# DC_Electronic_Load.net
KiCad netlist of a schematic drawn in EAGLE
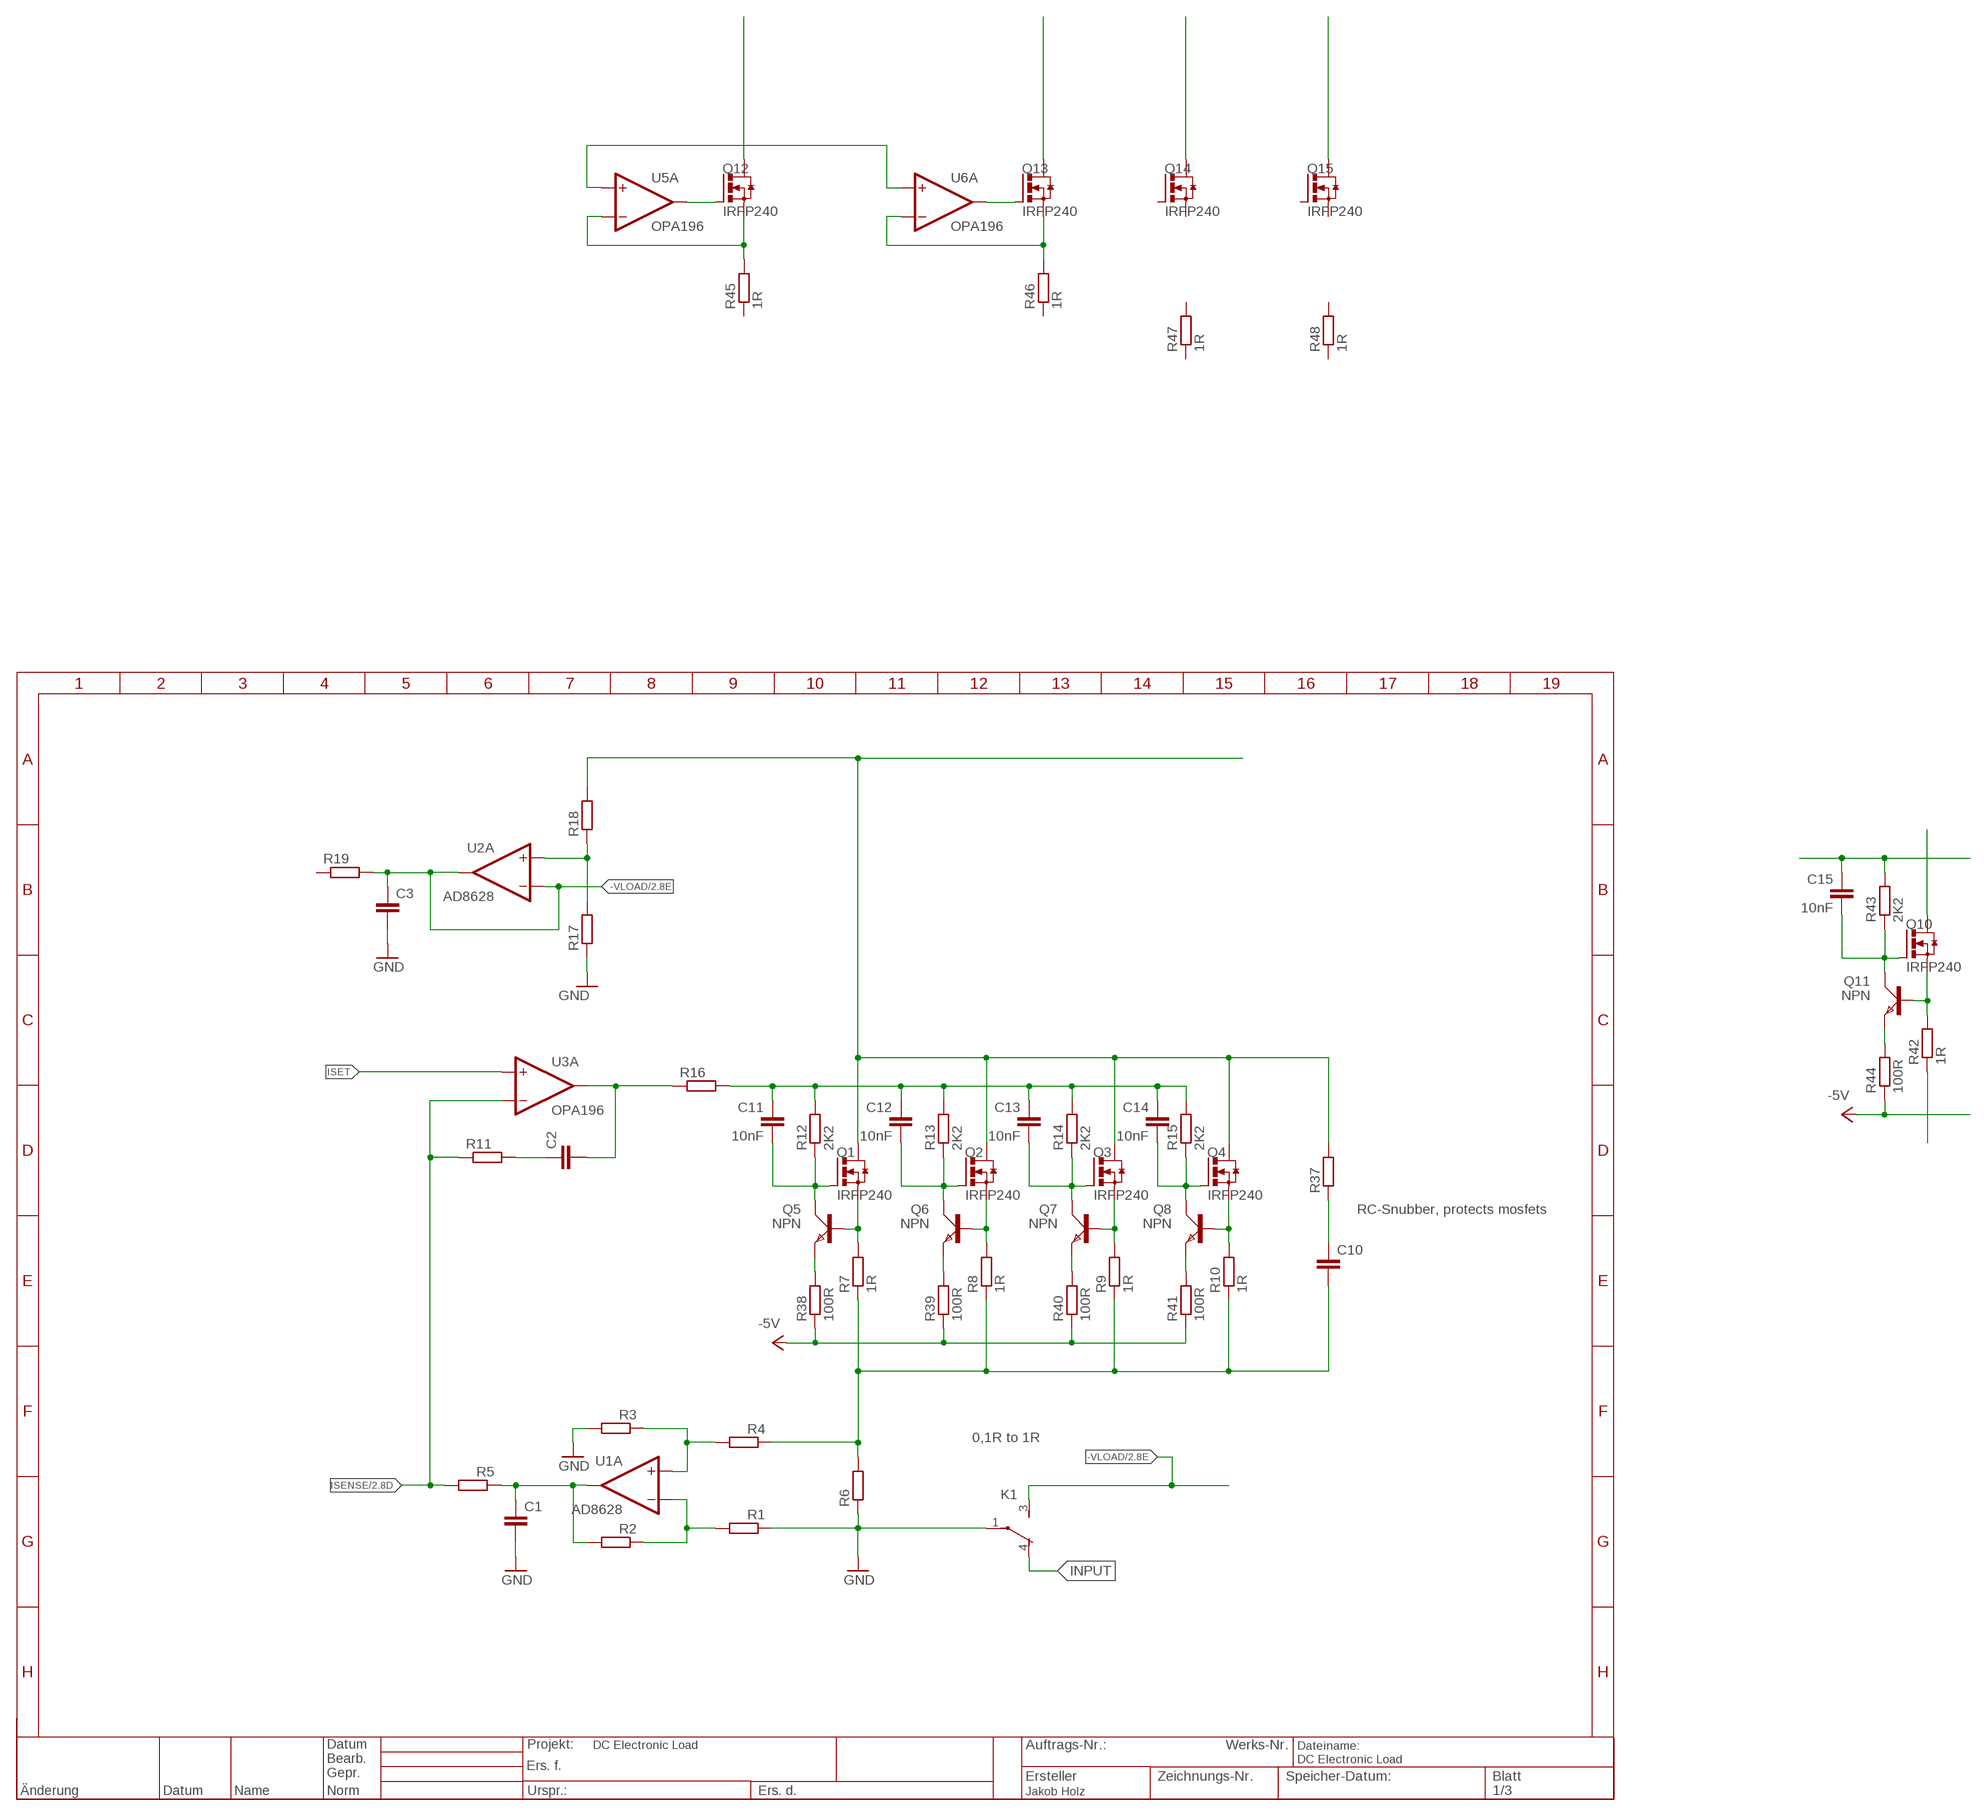
[diagram p0: schematic, sheet 1]
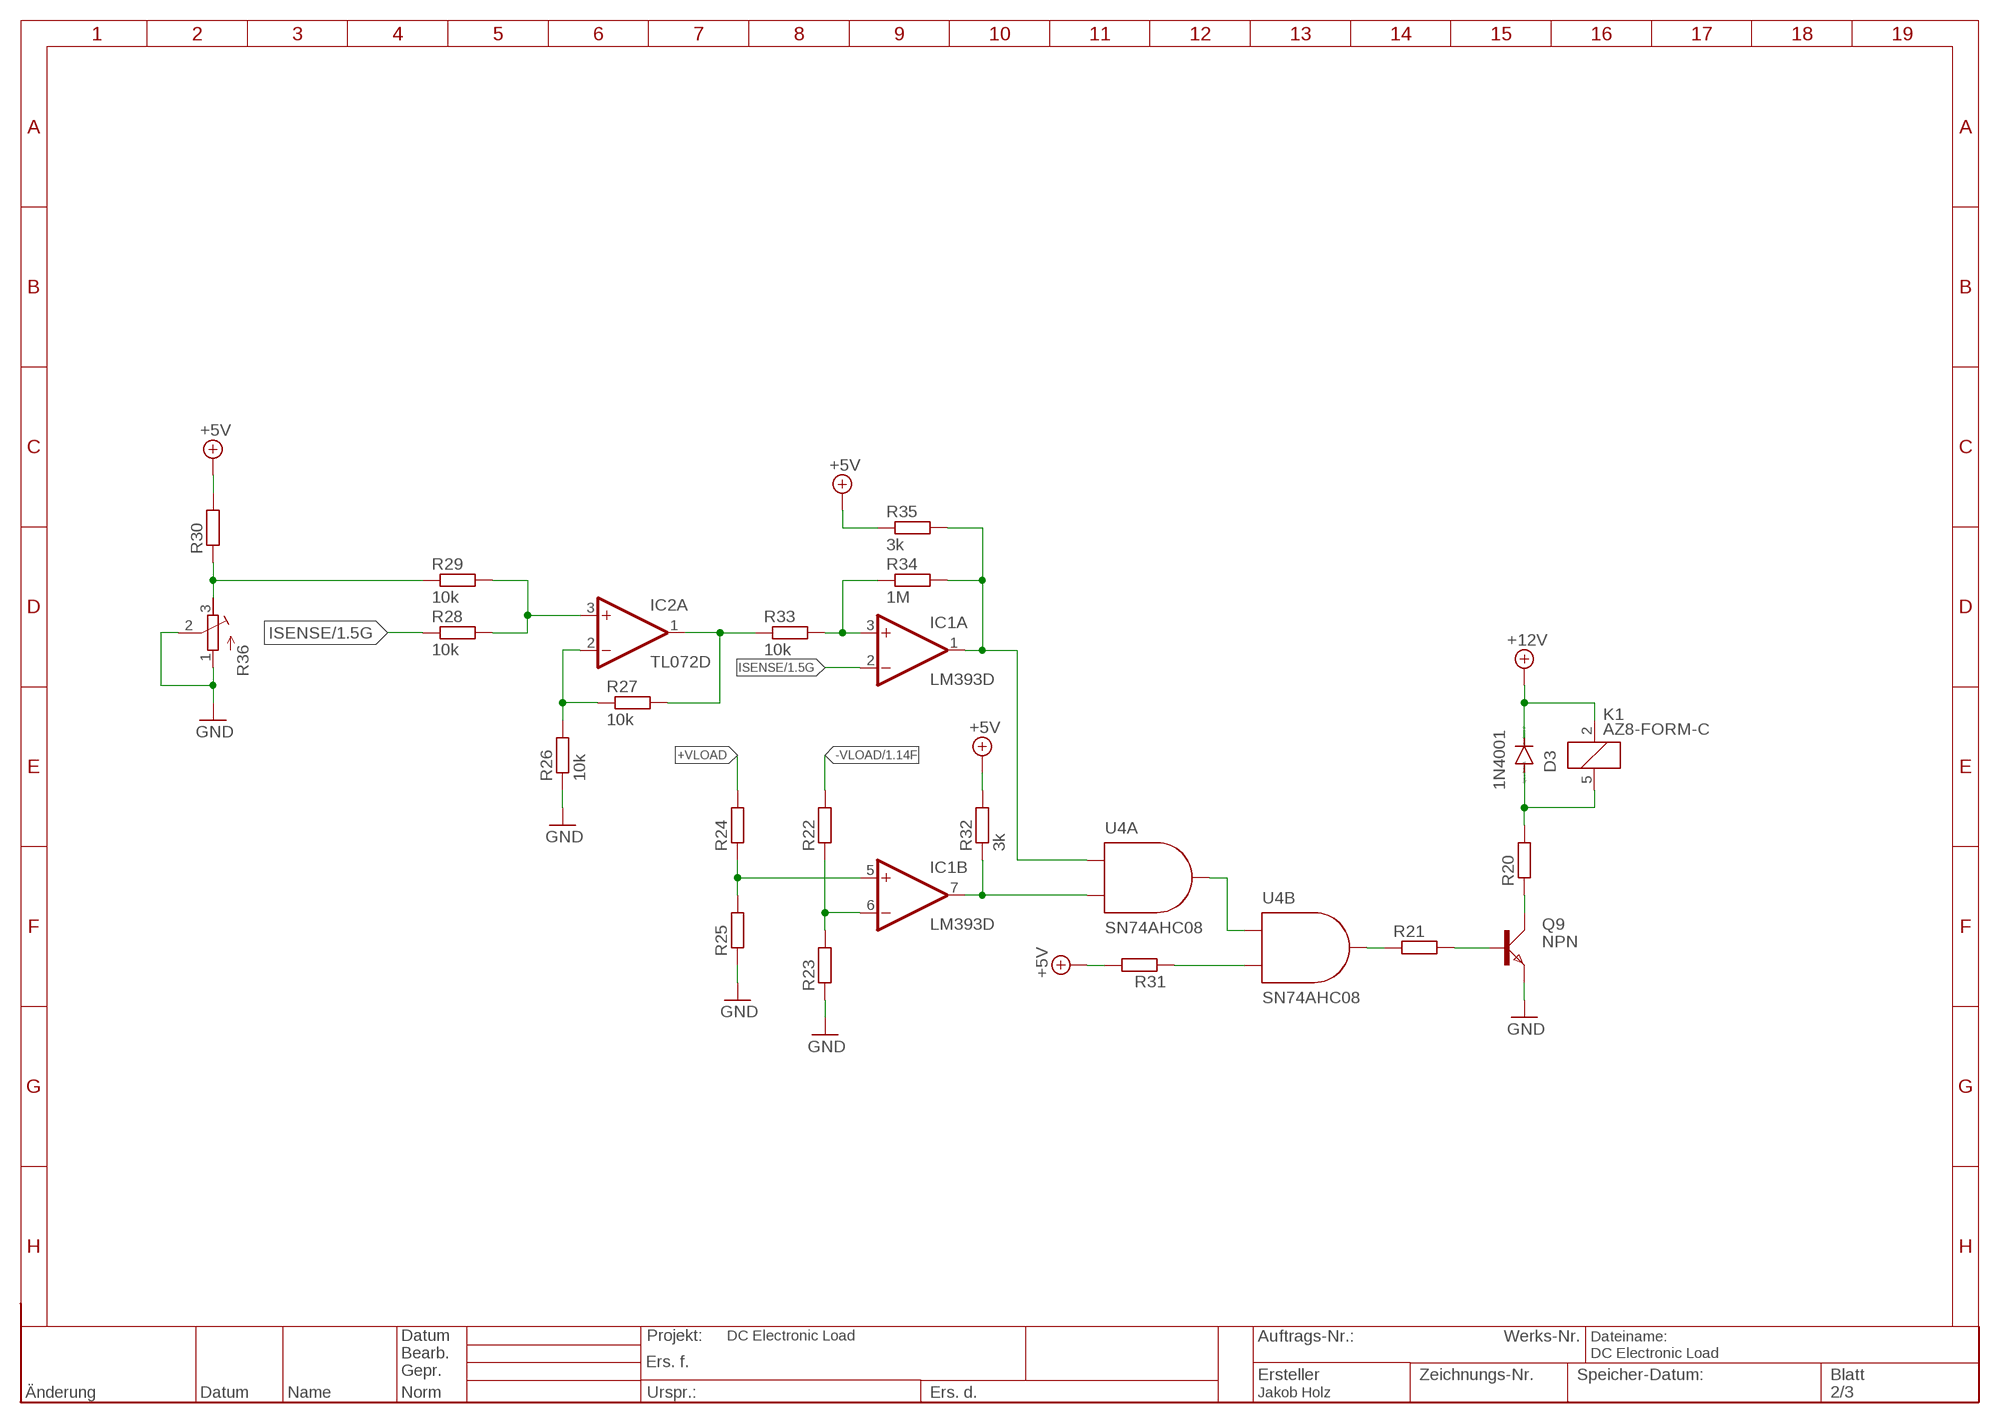
[diagram p1: schematic, sheet 2]
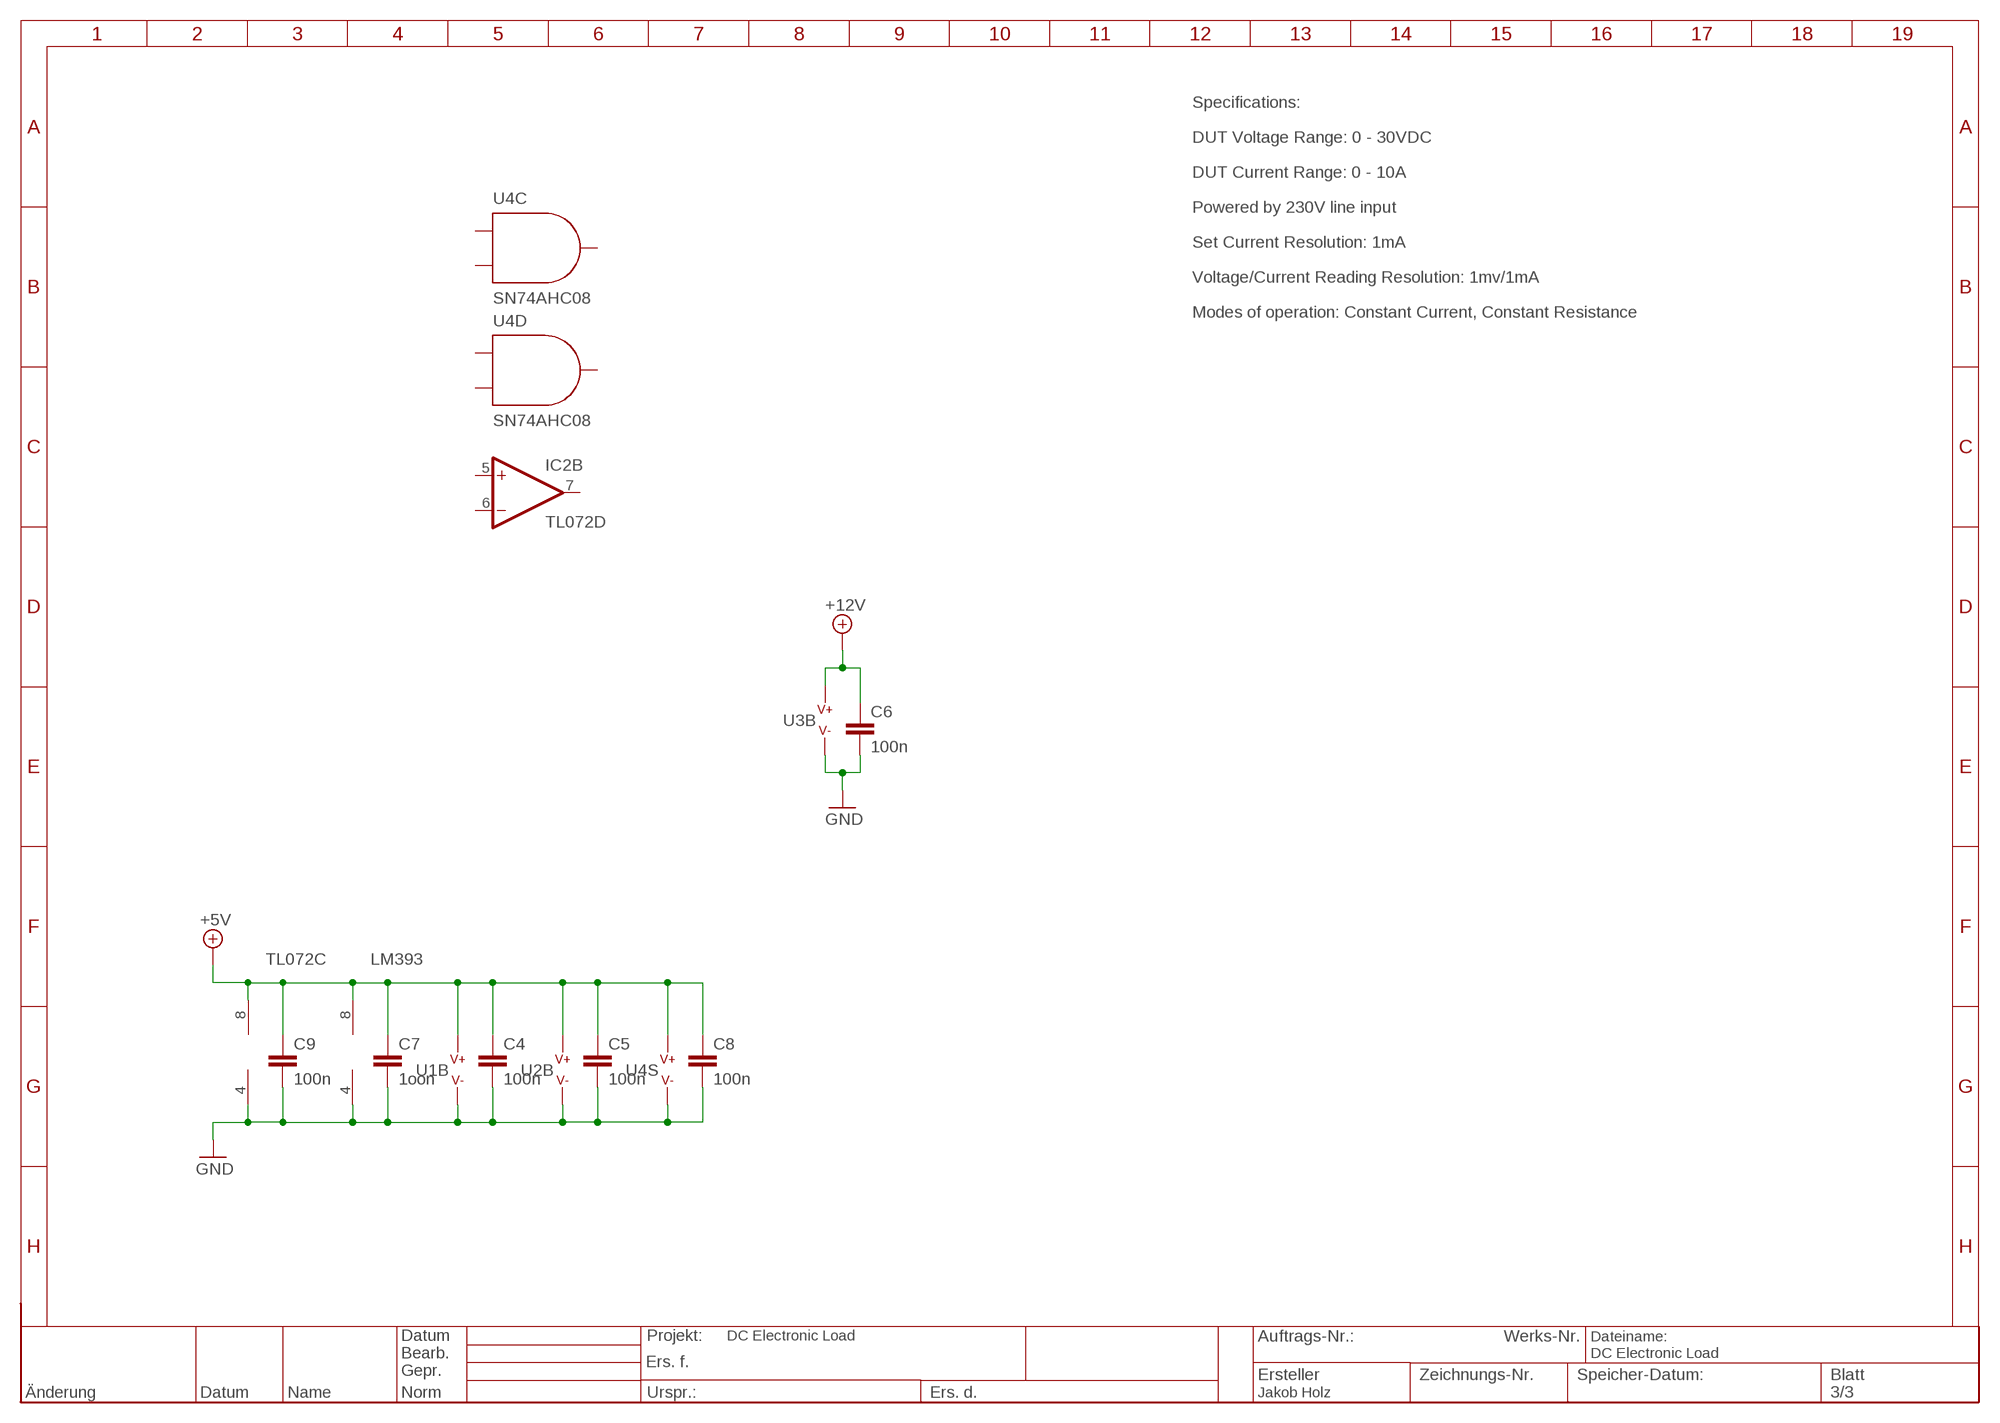
[diagram p2: schematic, sheet 3]

(export (version "E")
  (design (tool "Eeschema 10.0.6"))
  (components
    (comp (ref "D3")
      (value "1N4001")
      (footprint "eagle-import:MELF-MLL41")
      (libsource (lib "eagle-import") (part "DIODE-MELF-MLL41"))
    )
    (comp (ref "IC1")
      (value "LM393D")
      (footprint "eagle-import:SO08")
      (libsource (lib "eagle-import") (part "LM393D"))
    )
    (comp (ref "IC2")
      (value "TL072D")
      (footprint "eagle-import:SO08")
      (libsource (lib "eagle-import") (part "TL072D"))
    )
    (comp (ref "K1")
      (value "AZ8-FORM-C")
      (footprint "eagle-import:AZ8")
      (libsource (lib "eagle-import") (part "AZ8-FORM-C"))
    )
    (comp (ref "Q9")
      (value "NPN")
      (footprint "eagle-import:SOT23")
      (libsource (lib "eagle-import") (part "NPN"))
    )
    (comp (ref "R20")
      (value "R-EU_R1206")
      (footprint "eagle-import:R1206")
      (libsource (lib "eagle-import") (part "R-EU_R1206"))
    )
    (comp (ref "R21")
      (value "R-EU_R1206")
      (footprint "eagle-import:R1206")
      (libsource (lib "eagle-import") (part "R-EU_R1206"))
    )
    (comp (ref "R22")
      (value "R-EU_R1206")
      (footprint "eagle-import:R1206")
      (libsource (lib "eagle-import") (part "R-EU_R1206"))
    )
    (comp (ref "R23")
      (value "R-EU_R1206")
      (footprint "eagle-import:R1206")
      (libsource (lib "eagle-import") (part "R-EU_R1206"))
    )
    (comp (ref "R24")
      (value "R-EU_R1206")
      (footprint "eagle-import:R1206")
      (libsource (lib "eagle-import") (part "R-EU_R1206"))
    )
    (comp (ref "R25")
      (value "R-EU_R1206")
      (footprint "eagle-import:R1206")
      (libsource (lib "eagle-import") (part "R-EU_R1206"))
    )
    (comp (ref "R26")
      (value "10k")
      (footprint "eagle-import:R1206")
      (libsource (lib "eagle-import") (part "R-EU_R1206"))
    )
    (comp (ref "R27")
      (value "10k")
      (footprint "eagle-import:R1206")
      (libsource (lib "eagle-import") (part "R-EU_R1206"))
    )
    (comp (ref "R28")
      (value "10k")
      (footprint "eagle-import:R1206")
      (libsource (lib "eagle-import") (part "R-EU_R1206"))
    )
    (comp (ref "R29")
      (value "10k")
      (footprint "eagle-import:R1206")
      (libsource (lib "eagle-import") (part "R-EU_R1206"))
    )
    (comp (ref "R30")
      (value "R-EU_R1206")
      (footprint "eagle-import:R1206")
      (libsource (lib "eagle-import") (part "R-EU_R1206"))
    )
    (comp (ref "R31")
      (value "R-EU_R1206")
      (footprint "eagle-import:R1206")
      (libsource (lib "eagle-import") (part "R-EU_R1206"))
    )
    (comp (ref "R32")
      (value "3k")
      (footprint "eagle-import:R1206")
      (libsource (lib "eagle-import") (part "R-EU_R1206"))
    )
    (comp (ref "R33")
      (value "10k")
      (footprint "eagle-import:R1206")
      (libsource (lib "eagle-import") (part "R-EU_R1206"))
    )
    (comp (ref "R34")
      (value "1M")
      (footprint "eagle-import:R1206")
      (libsource (lib "eagle-import") (part "R-EU_R1206"))
    )
    (comp (ref "R35")
      (value "3k")
      (footprint "eagle-import:R1206")
      (libsource (lib "eagle-import") (part "R-EU_R1206"))
    )
    (comp (ref "R36")
      (value "R-TRIMM64W")
      (footprint "eagle-import:RTRIM64W")
      (libsource (lib "eagle-import") (part "R-TRIMM64W"))
    )
    (comp (ref "U4")
      (value "SN74AHC08")
      (footprint "eagle-import:SOIC−14")
      (libsource (lib "eagle-import") (part "SN74AHC08"))
    )
    (comp (ref "C1")
      (value "C-EUC1206")
      (footprint "eagle-import:C1206")
      (libsource (lib "eagle-import") (part "C-EUC1206"))
    )
    (comp (ref "C2")
      (value "C-EUC1206")
      (footprint "eagle-import:C1206")
      (libsource (lib "eagle-import") (part "C-EUC1206"))
    )
    (comp (ref "C3")
      (value "C-EUC1206")
      (footprint "eagle-import:C1206")
      (libsource (lib "eagle-import") (part "C-EUC1206"))
    )
    (comp (ref "C10")
      (value "C-EUC1206")
      (footprint "eagle-import:C1206")
      (libsource (lib "eagle-import") (part "C-EUC1206"))
    )
    (comp (ref "C11")
      (value "10nF")
      (footprint "eagle-import:C1206")
      (libsource (lib "eagle-import") (part "C-EUC1206"))
    )
    (comp (ref "C12")
      (value "10nF")
      (footprint "eagle-import:C1206")
      (libsource (lib "eagle-import") (part "C-EUC1206"))
    )
    (comp (ref "C13")
      (value "10nF")
      (footprint "eagle-import:C1206")
      (libsource (lib "eagle-import") (part "C-EUC1206"))
    )
    (comp (ref "C14")
      (value "10nF")
      (footprint "eagle-import:C1206")
      (libsource (lib "eagle-import") (part "C-EUC1206"))
    )
    (comp (ref "C15")
      (value "10nF")
      (footprint "eagle-import:C1206")
      (libsource (lib "eagle-import") (part "C-EUC1206"))
    )
    (comp (ref "Q1")
      (value "IRFP240")
      (footprint "eagle-import:TO247BV")
      (libsource (lib "eagle-import") (part "IRFP240"))
    )
    (comp (ref "Q2")
      (value "IRFP240")
      (footprint "eagle-import:TO247BV")
      (libsource (lib "eagle-import") (part "IRFP240"))
    )
    (comp (ref "Q3")
      (value "IRFP240")
      (footprint "eagle-import:TO247BV")
      (libsource (lib "eagle-import") (part "IRFP240"))
    )
    (comp (ref "Q4")
      (value "IRFP240")
      (footprint "eagle-import:TO247BV")
      (libsource (lib "eagle-import") (part "IRFP240"))
    )
    (comp (ref "Q5")
      (value "NPN")
      (footprint "eagle-import:SOT23")
      (libsource (lib "eagle-import") (part "NPN"))
    )
    (comp (ref "Q6")
      (value "NPN")
      (footprint "eagle-import:SOT23")
      (libsource (lib "eagle-import") (part "NPN"))
    )
    (comp (ref "Q7")
      (value "NPN")
      (footprint "eagle-import:SOT23")
      (libsource (lib "eagle-import") (part "NPN"))
    )
    (comp (ref "Q8")
      (value "NPN")
      (footprint "eagle-import:SOT23")
      (libsource (lib "eagle-import") (part "NPN"))
    )
    (comp (ref "Q10")
      (value "IRFP240")
      (footprint "eagle-import:TO247BV")
      (libsource (lib "eagle-import") (part "IRFP240"))
    )
    (comp (ref "Q11")
      (value "NPN")
      (footprint "eagle-import:SOT23")
      (libsource (lib "eagle-import") (part "NPN"))
    )
    (comp (ref "Q12")
      (value "IRFP240")
      (footprint "eagle-import:TO247BV")
      (libsource (lib "eagle-import") (part "IRFP240"))
    )
    (comp (ref "Q13")
      (value "IRFP240")
      (footprint "eagle-import:TO247BV")
      (libsource (lib "eagle-import") (part "IRFP240"))
    )
    (comp (ref "Q14")
      (value "IRFP240")
      (footprint "eagle-import:TO247BV")
      (libsource (lib "eagle-import") (part "IRFP240"))
    )
    (comp (ref "Q15")
      (value "IRFP240")
      (footprint "eagle-import:TO247BV")
      (libsource (lib "eagle-import") (part "IRFP240"))
    )
    (comp (ref "R1")
      (value "R-EU_R1206")
      (footprint "eagle-import:R1206")
      (libsource (lib "eagle-import") (part "R-EU_R1206"))
    )
    (comp (ref "R2")
      (value "R-EU_R1206")
      (footprint "eagle-import:R1206")
      (libsource (lib "eagle-import") (part "R-EU_R1206"))
    )
    (comp (ref "R3")
      (value "R-EU_R1206")
      (footprint "eagle-import:R1206")
      (libsource (lib "eagle-import") (part "R-EU_R1206"))
    )
    (comp (ref "R4")
      (value "R-EU_R1206")
      (footprint "eagle-import:R1206")
      (libsource (lib "eagle-import") (part "R-EU_R1206"))
    )
    (comp (ref "R5")
      (value "R-EU_R1206")
      (footprint "eagle-import:R1206")
      (libsource (lib "eagle-import") (part "R-EU_R1206"))
    )
    (comp (ref "R6")
      (value "R-EU_R1206")
      (footprint "eagle-import:R1206")
      (libsource (lib "eagle-import") (part "R-EU_R1206"))
    )
    (comp (ref "R7")
      (value "1R")
      (footprint "eagle-import:VTA53")
      (libsource (lib "eagle-import") (part "resistor_348_R-EU_VTA53"))
    )
    (comp (ref "R8")
      (value "1R")
      (footprint "eagle-import:VTA53")
      (libsource (lib "eagle-import") (part "resistor_348_R-EU_VTA53"))
    )
    (comp (ref "R9")
      (value "1R")
      (footprint "eagle-import:VTA53")
      (libsource (lib "eagle-import") (part "resistor_348_R-EU_VTA53"))
    )
    (comp (ref "R10")
      (value "1R")
      (footprint "eagle-import:VTA53")
      (libsource (lib "eagle-import") (part "resistor_348_R-EU_VTA53"))
    )
    (comp (ref "R11")
      (value "R-EU_R1206")
      (footprint "eagle-import:R1206")
      (libsource (lib "eagle-import") (part "R-EU_R1206"))
    )
    (comp (ref "R12")
      (value "2K2")
      (footprint "eagle-import:R1206")
      (libsource (lib "eagle-import") (part "R-EU_R1206"))
    )
    (comp (ref "R13")
      (value "2K2")
      (footprint "eagle-import:R1206")
      (libsource (lib "eagle-import") (part "R-EU_R1206"))
    )
    (comp (ref "R14")
      (value "2K2")
      (footprint "eagle-import:R1206")
      (libsource (lib "eagle-import") (part "R-EU_R1206"))
    )
    (comp (ref "R15")
      (value "2K2")
      (footprint "eagle-import:R1206")
      (libsource (lib "eagle-import") (part "R-EU_R1206"))
    )
    (comp (ref "R16")
      (value "R-EU_R1206")
      (footprint "eagle-import:R1206")
      (libsource (lib "eagle-import") (part "R-EU_R1206"))
    )
    (comp (ref "R17")
      (value "R-EU_R1206")
      (footprint "eagle-import:R1206")
      (libsource (lib "eagle-import") (part "R-EU_R1206"))
    )
    (comp (ref "R18")
      (value "R-EU_R1206")
      (footprint "eagle-import:R1206")
      (libsource (lib "eagle-import") (part "R-EU_R1206"))
    )
    (comp (ref "R19")
      (value "R-EU_R1206")
      (footprint "eagle-import:R1206")
      (libsource (lib "eagle-import") (part "R-EU_R1206"))
    )
    (comp (ref "R37")
      (value "R-EU_R1206")
      (footprint "eagle-import:R1206")
      (libsource (lib "eagle-import") (part "R-EU_R1206"))
    )
    (comp (ref "R38")
      (value "100R")
      (footprint "eagle-import:R1206")
      (libsource (lib "eagle-import") (part "R-EU_R1206"))
    )
    (comp (ref "R39")
      (value "100R")
      (footprint "eagle-import:R1206")
      (libsource (lib "eagle-import") (part "R-EU_R1206"))
    )
    (comp (ref "R40")
      (value "100R")
      (footprint "eagle-import:R1206")
      (libsource (lib "eagle-import") (part "R-EU_R1206"))
    )
    (comp (ref "R41")
      (value "100R")
      (footprint "eagle-import:R1206")
      (libsource (lib "eagle-import") (part "R-EU_R1206"))
    )
    (comp (ref "R42")
      (value "1R")
      (footprint "eagle-import:VTA53")
      (libsource (lib "eagle-import") (part "resistor_348_R-EU_VTA53"))
    )
    (comp (ref "R43")
      (value "2K2")
      (footprint "eagle-import:R1206")
      (libsource (lib "eagle-import") (part "R-EU_R1206"))
    )
    (comp (ref "R44")
      (value "100R")
      (footprint "eagle-import:R1206")
      (libsource (lib "eagle-import") (part "R-EU_R1206"))
    )
    (comp (ref "R45")
      (value "1R")
      (footprint "eagle-import:VTA53")
      (libsource (lib "eagle-import") (part "resistor_348_R-EU_VTA53"))
    )
    (comp (ref "R46")
      (value "1R")
      (footprint "eagle-import:VTA53")
      (libsource (lib "eagle-import") (part "resistor_348_R-EU_VTA53"))
    )
    (comp (ref "R47")
      (value "1R")
      (footprint "eagle-import:VTA53")
      (libsource (lib "eagle-import") (part "resistor_348_R-EU_VTA53"))
    )
    (comp (ref "R48")
      (value "1R")
      (footprint "eagle-import:VTA53")
      (libsource (lib "eagle-import") (part "resistor_348_R-EU_VTA53"))
    )
    (comp (ref "U1")
      (value "AD8628")
      (footprint "eagle-import:SOIC-8")
      (libsource (lib "eagle-import") (part "AD8628"))
    )
    (comp (ref "U2")
      (value "AD8628")
      (footprint "eagle-import:SOIC-8")
      (libsource (lib "eagle-import") (part "AD8628"))
    )
    (comp (ref "U3")
      (value "OPA196")
      (footprint "eagle-import:SOIC-8")
      (libsource (lib "eagle-import") (part "AD8628"))
    )
    (comp (ref "U5")
      (value "OPA196")
      (footprint "eagle-import:SOIC-8")
      (libsource (lib "eagle-import") (part "AD8628"))
    )
    (comp (ref "U6")
      (value "OPA196")
      (footprint "eagle-import:SOIC-8")
      (libsource (lib "eagle-import") (part "AD8628"))
    )
    (comp (ref "C4")
      (value "100n")
      (footprint "eagle-import:C1206")
      (libsource (lib "eagle-import") (part "C-EUC1206"))
    )
    (comp (ref "C5")
      (value "100n")
      (footprint "eagle-import:C1206")
      (libsource (lib "eagle-import") (part "C-EUC1206"))
    )
    (comp (ref "C6")
      (value "100n")
      (footprint "eagle-import:C1206")
      (libsource (lib "eagle-import") (part "C-EUC1206"))
    )
    (comp (ref "C7")
      (value "1oon")
      (footprint "eagle-import:C1206")
      (libsource (lib "eagle-import") (part "C-EUC1206"))
    )
    (comp (ref "C8")
      (value "100n")
      (footprint "eagle-import:C1206")
      (libsource (lib "eagle-import") (part "C-EUC1206"))
    )
    (comp (ref "C9")
      (value "100n")
      (footprint "eagle-import:C1206")
      (libsource (lib "eagle-import") (part "C-EUC1206"))
    )
  )
  (nets
    (net (code "1") (name "+5V") (class "Default")
      (node (ref "C4") (pin "1") (pinfunction "1_1") (pintype "passive"))
      (node (ref "C5") (pin "1") (pinfunction "1_1") (pintype "passive"))
      (node (ref "C7") (pin "1") (pinfunction "1_1") (pintype "passive"))
      (node (ref "C8") (pin "1") (pinfunction "1_1") (pintype "passive"))
      (node (ref "C9") (pin "1") (pinfunction "1_1") (pintype "passive"))
      (node (ref "IC1") (pin "8") (pinfunction "V+_8") (pintype "power_in"))
      (node (ref "IC2") (pin "8") (pinfunction "V+_8") (pintype "power_in"))
      (node (ref "R30") (pin "2") (pinfunction "2_2") (pintype "passive"))
      (node (ref "R31") (pin "2") (pinfunction "2_2") (pintype "passive"))
      (node (ref "R32") (pin "2") (pinfunction "2_2") (pintype "passive"))
      (node (ref "R35") (pin "1") (pinfunction "1_1") (pintype "passive"))
      (node (ref "U1") (pin "7") (pinfunction "V+_7") (pintype "bidirectional"))
      (node (ref "U2") (pin "7") (pinfunction "V+_7") (pintype "bidirectional"))
      (node (ref "U4") (pin "14") (pinfunction "V+_14") (pintype "bidirectional"))
    )
    (net (code "2") (name "+12V") (class "Default")
      (node (ref "C6") (pin "1") (pinfunction "1_1") (pintype "passive"))
      (node (ref "D3") (pin "C") (pinfunction "C_C") (pintype "passive"))
      (node (ref "K1") (pin "2") (pinfunction "1_2") (pintype "passive"))
      (node (ref "U3") (pin "7") (pinfunction "V+_7") (pintype "bidirectional"))
    )
    (net (code "3") (name "+VLOAD") (class "Default")
      (node (ref "Q1") (pin "D") (pinfunction "D_D") (pintype "passive"))
      (node (ref "Q2") (pin "D") (pinfunction "D_D") (pintype "passive"))
      (node (ref "Q3") (pin "D") (pinfunction "D_D") (pintype "passive"))
      (node (ref "Q4") (pin "D") (pinfunction "D_D") (pintype "passive"))
      (node (ref "R18") (pin "2") (pinfunction "2_2") (pintype "passive"))
      (node (ref "R24") (pin "2") (pinfunction "2_2") (pintype "passive"))
      (node (ref "R37") (pin "2") (pinfunction "2_2") (pintype "passive"))
    )
    (net (code "4") (name "-5V") (class "Default")
      (node (ref "R38") (pin "1") (pinfunction "1_1") (pintype "passive"))
      (node (ref "R39") (pin "1") (pinfunction "1_1") (pintype "passive"))
      (node (ref "R40") (pin "1") (pinfunction "1_1") (pintype "passive"))
      (node (ref "R41") (pin "1") (pinfunction "1_1") (pintype "passive"))
      (node (ref "R44") (pin "1") (pinfunction "1_1") (pintype "passive"))
    )
    (net (code "5") (name "-VLOAD") (class "Default")
      (node (ref "C3") (pin "1") (pinfunction "1_1") (pintype "passive"))
      (node (ref "K1") (pin "3") (pinfunction "S_3") (pintype "passive"))
      (node (ref "R19") (pin "2") (pinfunction "2_2") (pintype "passive"))
      (node (ref "R22") (pin "2") (pinfunction "2_2") (pintype "passive"))
      (node (ref "U2") (pin "2") (pinfunction "IN-_2") (pintype "bidirectional"))
      (node (ref "U2") (pin "6") (pinfunction "OUT_6") (pintype "bidirectional"))
    )
    (net (code "6") (name "GND") (class "Default")
      (node (ref "C1") (pin "2") (pinfunction "2_2") (pintype "passive"))
      (node (ref "C3") (pin "2") (pinfunction "2_2") (pintype "passive"))
      (node (ref "C4") (pin "2") (pinfunction "2_2") (pintype "passive"))
      (node (ref "C5") (pin "2") (pinfunction "2_2") (pintype "passive"))
      (node (ref "C6") (pin "2") (pinfunction "2_2") (pintype "passive"))
      (node (ref "C7") (pin "2") (pinfunction "2_2") (pintype "passive"))
      (node (ref "C8") (pin "2") (pinfunction "2_2") (pintype "passive"))
      (node (ref "C9") (pin "2") (pinfunction "2_2") (pintype "passive"))
      (node (ref "IC1") (pin "4") (pinfunction "V-_4") (pintype "power_in"))
      (node (ref "IC2") (pin "4") (pinfunction "V-_4") (pintype "power_in"))
      (node (ref "K1") (pin "1") (pinfunction "P_1") (pintype "passive"))
      (node (ref "Q9") (pin "2") (pinfunction "E_2") (pintype "passive"))
      (node (ref "R1") (pin "1") (pinfunction "1_1") (pintype "passive"))
      (node (ref "R17") (pin "1") (pinfunction "1_1") (pintype "passive"))
      (node (ref "R23") (pin "1") (pinfunction "1_1") (pintype "passive"))
      (node (ref "R25") (pin "1") (pinfunction "1_1") (pintype "passive"))
      (node (ref "R26") (pin "1") (pinfunction "1_1") (pintype "passive"))
      (node (ref "R3") (pin "2") (pinfunction "2_2") (pintype "passive"))
      (node (ref "R36") (pin "1") (pinfunction "A_1") (pintype "passive"))
      (node (ref "R36") (pin "2") (pinfunction "S_2") (pintype "passive"))
      (node (ref "R6") (pin "1") (pinfunction "1_1") (pintype "passive"))
      (node (ref "U1") (pin "4") (pinfunction "V-_4") (pintype "bidirectional"))
      (node (ref "U2") (pin "4") (pinfunction "V-_4") (pintype "bidirectional"))
      (node (ref "U3") (pin "4") (pinfunction "V-_4") (pintype "bidirectional"))
      (node (ref "U4") (pin "7") (pinfunction "V-_7") (pintype "bidirectional"))
    )
    (net (code "7") (name "INPUT") (class "Default")
      (node (ref "K1") (pin "4") (pinfunction "O_4") (pintype "passive"))
    )
    (net (code "8") (name "ISENSE") (class "Default")
      (node (ref "IC1") (pin "2") (pinfunction "-IN_2") (pintype "input"))
      (node (ref "R11") (pin "1") (pinfunction "1_1") (pintype "passive"))
      (node (ref "R28") (pin "1") (pinfunction "1_1") (pintype "passive"))
      (node (ref "R5") (pin "2") (pinfunction "2_2") (pintype "passive"))
      (node (ref "U3") (pin "2") (pinfunction "IN-_2") (pintype "bidirectional"))
    )
    (net (code "9") (name "ISET") (class "Default")
      (node (ref "U3") (pin "3") (pinfunction "IN+_3") (pintype "bidirectional"))
    )
    (net (code "10") (name "Net-(C2-Pad1)") (class "Default")
      (node (ref "C2") (pin "1") (pinfunction "1_1") (pintype "passive"))
      (node (ref "R11") (pin "2") (pinfunction "2_2") (pintype "passive"))
    )
    (net (code "11") (name "Net-(C10-Pad1)") (class "Default")
      (node (ref "C10") (pin "1") (pinfunction "1_1") (pintype "passive"))
      (node (ref "R37") (pin "1") (pinfunction "1_1") (pintype "passive"))
    )
    (net (code "12") (name "Net-(C10-Pad2)") (class "Default")
      (node (ref "C10") (pin "2") (pinfunction "2_2") (pintype "passive"))
      (node (ref "R10") (pin "1") (pinfunction "1_1") (pintype "passive"))
      (node (ref "R4") (pin "1") (pinfunction "1_1") (pintype "passive"))
      (node (ref "R6") (pin "2") (pinfunction "2_2") (pintype "passive"))
      (node (ref "R7") (pin "1") (pinfunction "1_1") (pintype "passive"))
      (node (ref "R8") (pin "1") (pinfunction "1_1") (pintype "passive"))
      (node (ref "R9") (pin "1") (pinfunction "1_1") (pintype "passive"))
    )
    (net (code "13") (name "Net-(C11-Pad1)") (class "Default")
      (node (ref "C11") (pin "1") (pinfunction "1_1") (pintype "passive"))
      (node (ref "C12") (pin "1") (pinfunction "1_1") (pintype "passive"))
      (node (ref "C13") (pin "1") (pinfunction "1_1") (pintype "passive"))
      (node (ref "C14") (pin "1") (pinfunction "1_1") (pintype "passive"))
      (node (ref "R12") (pin "2") (pinfunction "2_2") (pintype "passive"))
      (node (ref "R13") (pin "2") (pinfunction "2_2") (pintype "passive"))
      (node (ref "R14") (pin "2") (pinfunction "2_2") (pintype "passive"))
      (node (ref "R15") (pin "2") (pinfunction "2_2") (pintype "passive"))
      (node (ref "R16") (pin "2") (pinfunction "2_2") (pintype "passive"))
    )
    (net (code "14") (name "Net-(C15-Pad1)") (class "Default")
      (node (ref "C15") (pin "1") (pinfunction "1_1") (pintype "passive"))
      (node (ref "R43") (pin "2") (pinfunction "2_2") (pintype "passive"))
    )
    (net (code "15") (name "Net-(IC1A-+IN)") (class "Default")
      (node (ref "IC1") (pin "3") (pinfunction "+IN_3") (pintype "input"))
      (node (ref "R33") (pin "2") (pinfunction "2_2") (pintype "passive"))
      (node (ref "R34") (pin "1") (pinfunction "1_1") (pintype "passive"))
    )
    (net (code "16") (name "Net-(IC1A-OUT)") (class "Default")
      (node (ref "IC1") (pin "1") (pinfunction "OUT_1") (pintype "output"))
      (node (ref "R34") (pin "2") (pinfunction "2_2") (pintype "passive"))
      (node (ref "R35") (pin "2") (pinfunction "2_2") (pintype "passive"))
      (node (ref "U4") (pin "1") (pinfunction "A_1") (pintype "input"))
    )
    (net (code "17") (name "Net-(IC1B-+IN)") (class "Default")
      (node (ref "IC1") (pin "5") (pinfunction "+IN_5") (pintype "input"))
      (node (ref "R24") (pin "1") (pinfunction "1_1") (pintype "passive"))
      (node (ref "R25") (pin "2") (pinfunction "2_2") (pintype "passive"))
    )
    (net (code "18") (name "Net-(IC1B--IN)") (class "Default")
      (node (ref "IC1") (pin "6") (pinfunction "-IN_6") (pintype "input"))
      (node (ref "R22") (pin "1") (pinfunction "1_1") (pintype "passive"))
      (node (ref "R23") (pin "2") (pinfunction "2_2") (pintype "passive"))
    )
    (net (code "19") (name "Net-(IC1B-OUT)") (class "Default")
      (node (ref "IC1") (pin "7") (pinfunction "OUT_7") (pintype "output"))
      (node (ref "R32") (pin "1") (pinfunction "1_1") (pintype "passive"))
      (node (ref "U4") (pin "2") (pinfunction "B_2") (pintype "input"))
    )
    (net (code "20") (name "Net-(IC2A-+IN)") (class "Default")
      (node (ref "IC2") (pin "3") (pinfunction "+IN_3") (pintype "input"))
      (node (ref "R28") (pin "2") (pinfunction "2_2") (pintype "passive"))
      (node (ref "R29") (pin "2") (pinfunction "2_2") (pintype "passive"))
    )
    (net (code "21") (name "Net-(IC2A--IN)") (class "Default")
      (node (ref "IC2") (pin "2") (pinfunction "-IN_2") (pintype "input"))
      (node (ref "R26") (pin "2") (pinfunction "2_2") (pintype "passive"))
      (node (ref "R27") (pin "1") (pinfunction "1_1") (pintype "passive"))
    )
    (net (code "22") (name "Net-(IC2A-OUT)") (class "Default")
      (node (ref "IC2") (pin "1") (pinfunction "OUT_1") (pintype "output"))
      (node (ref "R27") (pin "2") (pinfunction "2_2") (pintype "passive"))
      (node (ref "R33") (pin "1") (pinfunction "1_1") (pintype "passive"))
    )
    (net (code "23") (name "Net-(K1B-2)") (class "Default")
      (node (ref "D3") (pin "A") (pinfunction "A_A") (pintype "passive"))
      (node (ref "K1") (pin "5") (pinfunction "2_5") (pintype "passive"))
      (node (ref "R20") (pin "2") (pinfunction "2_2") (pintype "passive"))
    )
    (net (code "24") (name "Net-(Q5-B)") (class "Default")
      (node (ref "Q1") (pin "S") (pinfunction "S_S") (pintype "passive"))
      (node (ref "Q5") (pin "1") (pinfunction "B_1") (pintype "bidirectional"))
      (node (ref "R7") (pin "2") (pinfunction "2_2") (pintype "passive"))
    )
    (net (code "25") (name "Net-(Q5-C)") (class "Default")
      (node (ref "C11") (pin "2") (pinfunction "2_2") (pintype "passive"))
      (node (ref "Q1") (pin "G") (pinfunction "G_G") (pintype "passive"))
      (node (ref "Q5") (pin "3") (pinfunction "C_3") (pintype "passive"))
      (node (ref "R12") (pin "1") (pinfunction "1_1") (pintype "passive"))
    )
    (net (code "26") (name "Net-(Q5-E)") (class "Default")
      (node (ref "Q5") (pin "2") (pinfunction "E_2") (pintype "passive"))
      (node (ref "R38") (pin "2") (pinfunction "2_2") (pintype "passive"))
    )
    (net (code "27") (name "Net-(Q6-B)") (class "Default")
      (node (ref "Q2") (pin "S") (pinfunction "S_S") (pintype "passive"))
      (node (ref "Q6") (pin "1") (pinfunction "B_1") (pintype "bidirectional"))
      (node (ref "R8") (pin "2") (pinfunction "2_2") (pintype "passive"))
    )
    (net (code "28") (name "Net-(Q6-C)") (class "Default")
      (node (ref "C12") (pin "2") (pinfunction "2_2") (pintype "passive"))
      (node (ref "Q2") (pin "G") (pinfunction "G_G") (pintype "passive"))
      (node (ref "Q6") (pin "3") (pinfunction "C_3") (pintype "passive"))
      (node (ref "R13") (pin "1") (pinfunction "1_1") (pintype "passive"))
    )
    (net (code "29") (name "Net-(Q6-E)") (class "Default")
      (node (ref "Q6") (pin "2") (pinfunction "E_2") (pintype "passive"))
      (node (ref "R39") (pin "2") (pinfunction "2_2") (pintype "passive"))
    )
    (net (code "30") (name "Net-(Q7-B)") (class "Default")
      (node (ref "Q3") (pin "S") (pinfunction "S_S") (pintype "passive"))
      (node (ref "Q7") (pin "1") (pinfunction "B_1") (pintype "bidirectional"))
      (node (ref "R9") (pin "2") (pinfunction "2_2") (pintype "passive"))
    )
    (net (code "31") (name "Net-(Q7-C)") (class "Default")
      (node (ref "C13") (pin "2") (pinfunction "2_2") (pintype "passive"))
      (node (ref "Q3") (pin "G") (pinfunction "G_G") (pintype "passive"))
      (node (ref "Q7") (pin "3") (pinfunction "C_3") (pintype "passive"))
      (node (ref "R14") (pin "1") (pinfunction "1_1") (pintype "passive"))
    )
    (net (code "32") (name "Net-(Q7-E)") (class "Default")
      (node (ref "Q7") (pin "2") (pinfunction "E_2") (pintype "passive"))
      (node (ref "R40") (pin "2") (pinfunction "2_2") (pintype "passive"))
    )
    (net (code "33") (name "Net-(Q8-B)") (class "Default")
      (node (ref "Q4") (pin "S") (pinfunction "S_S") (pintype "passive"))
      (node (ref "Q8") (pin "1") (pinfunction "B_1") (pintype "bidirectional"))
      (node (ref "R10") (pin "2") (pinfunction "2_2") (pintype "passive"))
    )
    (net (code "34") (name "Net-(Q8-C)") (class "Default")
      (node (ref "C14") (pin "2") (pinfunction "2_2") (pintype "passive"))
      (node (ref "Q4") (pin "G") (pinfunction "G_G") (pintype "passive"))
      (node (ref "Q8") (pin "3") (pinfunction "C_3") (pintype "passive"))
      (node (ref "R15") (pin "1") (pinfunction "1_1") (pintype "passive"))
    )
    (net (code "35") (name "Net-(Q8-E)") (class "Default")
      (node (ref "Q8") (pin "2") (pinfunction "E_2") (pintype "passive"))
      (node (ref "R41") (pin "2") (pinfunction "2_2") (pintype "passive"))
    )
    (net (code "36") (name "Net-(Q9-B)") (class "Default")
      (node (ref "Q9") (pin "1") (pinfunction "B_1") (pintype "bidirectional"))
      (node (ref "R21") (pin "2") (pinfunction "2_2") (pintype "passive"))
    )
    (net (code "37") (name "Net-(Q9-C)") (class "Default")
      (node (ref "Q9") (pin "3") (pinfunction "C_3") (pintype "passive"))
      (node (ref "R20") (pin "1") (pinfunction "1_1") (pintype "passive"))
    )
    (net (code "38") (name "Net-(Q11-B)") (class "Default")
      (node (ref "Q10") (pin "S") (pinfunction "S_S") (pintype "passive"))
      (node (ref "Q11") (pin "1") (pinfunction "B_1") (pintype "bidirectional"))
      (node (ref "R42") (pin "2") (pinfunction "2_2") (pintype "passive"))
    )
    (net (code "39") (name "Net-(Q11-C)") (class "Default")
      (node (ref "C15") (pin "2") (pinfunction "2_2") (pintype "passive"))
      (node (ref "Q10") (pin "G") (pinfunction "G_G") (pintype "passive"))
      (node (ref "Q11") (pin "3") (pinfunction "C_3") (pintype "passive"))
      (node (ref "R43") (pin "1") (pinfunction "1_1") (pintype "passive"))
    )
    (net (code "40") (name "Net-(Q11-E)") (class "Default")
      (node (ref "Q11") (pin "2") (pinfunction "E_2") (pintype "passive"))
      (node (ref "R44") (pin "2") (pinfunction "2_2") (pintype "passive"))
    )
    (net (code "41") (name "Net-(R36-E)") (class "Default")
      (node (ref "R29") (pin "1") (pinfunction "1_1") (pintype "passive"))
      (node (ref "R30") (pin "1") (pinfunction "1_1") (pintype "passive"))
      (node (ref "R36") (pin "3") (pinfunction "E_3") (pintype "passive"))
    )
    (net (code "42") (name "Net-(U1A-IN+)") (class "Default")
      (node (ref "R3") (pin "1") (pinfunction "1_1") (pintype "passive"))
      (node (ref "R4") (pin "2") (pinfunction "2_2") (pintype "passive"))
      (node (ref "U1") (pin "3") (pinfunction "IN+_3") (pintype "bidirectional"))
    )
    (net (code "43") (name "Net-(U1A-IN-)") (class "Default")
      (node (ref "R1") (pin "2") (pinfunction "2_2") (pintype "passive"))
      (node (ref "R2") (pin "1") (pinfunction "1_1") (pintype "passive"))
      (node (ref "U1") (pin "2") (pinfunction "IN-_2") (pintype "bidirectional"))
    )
    (net (code "44") (name "Net-(U1A-OUT)") (class "Default")
      (node (ref "C1") (pin "1") (pinfunction "1_1") (pintype "passive"))
      (node (ref "R2") (pin "2") (pinfunction "2_2") (pintype "passive"))
      (node (ref "R5") (pin "1") (pinfunction "1_1") (pintype "passive"))
      (node (ref "U1") (pin "6") (pinfunction "OUT_6") (pintype "bidirectional"))
    )
    (net (code "45") (name "Net-(U2A-IN+)") (class "Default")
      (node (ref "R17") (pin "2") (pinfunction "2_2") (pintype "passive"))
      (node (ref "R18") (pin "1") (pinfunction "1_1") (pintype "passive"))
      (node (ref "U2") (pin "3") (pinfunction "IN+_3") (pintype "bidirectional"))
    )
    (net (code "46") (name "Net-(U3A-OUT)") (class "Default")
      (node (ref "C2") (pin "2") (pinfunction "2_2") (pintype "passive"))
      (node (ref "R16") (pin "1") (pinfunction "1_1") (pintype "passive"))
      (node (ref "U3") (pin "6") (pinfunction "OUT_6") (pintype "bidirectional"))
    )
    (net (code "47") (name "Net-(U4A-Y)") (class "Default")
      (node (ref "U4") (pin "3") (pinfunction "Y_3") (pintype "bidirectional"))
      (node (ref "U4") (pin "4") (pinfunction "A_4") (pintype "input"))
    )
    (net (code "48") (name "Net-(U4B-B)") (class "Default")
      (node (ref "R31") (pin "1") (pinfunction "1_1") (pintype "passive"))
      (node (ref "U4") (pin "5") (pinfunction "B_5") (pintype "input"))
    )
    (net (code "49") (name "Net-(U4B-Y)") (class "Default")
      (node (ref "R21") (pin "1") (pinfunction "1_1") (pintype "passive"))
      (node (ref "U4") (pin "6") (pinfunction "Y_6") (pintype "bidirectional"))
    )
    (net (code "50") (name "Net-(U5A-IN+)") (class "Default")
      (node (ref "U5") (pin "3") (pinfunction "IN+_3") (pintype "bidirectional"))
      (node (ref "U6") (pin "3") (pinfunction "IN+_3") (pintype "bidirectional"))
    )
    (net (code "51") (name "Net-(U5A-IN-)") (class "Default")
      (node (ref "Q12") (pin "S") (pinfunction "S_S") (pintype "passive"))
      (node (ref "R45") (pin "2") (pinfunction "2_2") (pintype "passive"))
      (node (ref "U5") (pin "2") (pinfunction "IN-_2") (pintype "bidirectional"))
    )
    (net (code "52") (name "Net-(U5A-OUT)") (class "Default")
      (node (ref "Q12") (pin "G") (pinfunction "G_G") (pintype "passive"))
      (node (ref "U5") (pin "6") (pinfunction "OUT_6") (pintype "bidirectional"))
    )
    (net (code "53") (name "Net-(U6A-IN-)") (class "Default")
      (node (ref "Q13") (pin "S") (pinfunction "S_S") (pintype "passive"))
      (node (ref "R46") (pin "2") (pinfunction "2_2") (pintype "passive"))
      (node (ref "U6") (pin "2") (pinfunction "IN-_2") (pintype "bidirectional"))
    )
    (net (code "54") (name "Net-(U6A-OUT)") (class "Default")
      (node (ref "Q13") (pin "G") (pinfunction "G_G") (pintype "passive"))
      (node (ref "U6") (pin "6") (pinfunction "OUT_6") (pintype "bidirectional"))
    )
    (net (code "55") (name "unconnected-(IC2B-+IN-Pad5)") (class "Default")
      (node (ref "IC2") (pin "5") (pinfunction "+IN_5") (pintype "input"))
    )
    (net (code "56") (name "unconnected-(IC2B--IN-Pad6)") (class "Default")
      (node (ref "IC2") (pin "6") (pinfunction "-IN_6") (pintype "input"))
    )
    (net (code "57") (name "unconnected-(IC2B-OUT-Pad7)") (class "Default")
      (node (ref "IC2") (pin "7") (pinfunction "OUT_7") (pintype "output"))
    )
    (net (code "58") (name "unconnected-(Q10-PadD)") (class "Default")
      (node (ref "Q10") (pin "D") (pinfunction "D_D") (pintype "passive"))
    )
    (net (code "59") (name "unconnected-(Q12-PadD)") (class "Default")
      (node (ref "Q12") (pin "D") (pinfunction "D_D") (pintype "passive"))
    )
    (net (code "60") (name "unconnected-(Q13-PadD)") (class "Default")
      (node (ref "Q13") (pin "D") (pinfunction "D_D") (pintype "passive"))
    )
    (net (code "61") (name "unconnected-(Q14-PadD)") (class "Default")
      (node (ref "Q14") (pin "D") (pinfunction "D_D") (pintype "passive"))
    )
    (net (code "62") (name "unconnected-(Q14-PadG)") (class "Default")
      (node (ref "Q14") (pin "G") (pinfunction "G_G") (pintype "passive"))
    )
    (net (code "63") (name "unconnected-(Q14-PadS)") (class "Default")
      (node (ref "Q14") (pin "S") (pinfunction "S_S") (pintype "passive"))
    )
    (net (code "64") (name "unconnected-(Q15-PadD)") (class "Default")
      (node (ref "Q15") (pin "D") (pinfunction "D_D") (pintype "passive"))
    )
    (net (code "65") (name "unconnected-(Q15-PadG)") (class "Default")
      (node (ref "Q15") (pin "G") (pinfunction "G_G") (pintype "passive"))
    )
    (net (code "66") (name "unconnected-(Q15-PadS)") (class "Default")
      (node (ref "Q15") (pin "S") (pinfunction "S_S") (pintype "passive"))
    )
    (net (code "67") (name "unconnected-(R19-Pad1)") (class "Default")
      (node (ref "R19") (pin "1") (pinfunction "1_1") (pintype "passive"))
    )
    (net (code "68") (name "unconnected-(R42-Pad1)") (class "Default")
      (node (ref "R42") (pin "1") (pinfunction "1_1") (pintype "passive"))
    )
    (net (code "69") (name "unconnected-(R45-Pad1)") (class "Default")
      (node (ref "R45") (pin "1") (pinfunction "1_1") (pintype "passive"))
    )
    (net (code "70") (name "unconnected-(R46-Pad1)") (class "Default")
      (node (ref "R46") (pin "1") (pinfunction "1_1") (pintype "passive"))
    )
    (net (code "71") (name "unconnected-(R47-Pad1)") (class "Default")
      (node (ref "R47") (pin "1") (pinfunction "1_1") (pintype "passive"))
    )
    (net (code "72") (name "unconnected-(R47-Pad2)") (class "Default")
      (node (ref "R47") (pin "2") (pinfunction "2_2") (pintype "passive"))
    )
    (net (code "73") (name "unconnected-(R48-Pad1)") (class "Default")
      (node (ref "R48") (pin "1") (pinfunction "1_1") (pintype "passive"))
    )
    (net (code "74") (name "unconnected-(R48-Pad2)") (class "Default")
      (node (ref "R48") (pin "2") (pinfunction "2_2") (pintype "passive"))
    )
    (net (code "75") (name "unconnected-(U4C-A-Pad9)") (class "Default")
      (node (ref "U4") (pin "9") (pinfunction "A_9") (pintype "input"))
    )
    (net (code "76") (name "unconnected-(U4C-B-Pad10)") (class "Default")
      (node (ref "U4") (pin "10") (pinfunction "B_10") (pintype "input"))
    )
    (net (code "77") (name "unconnected-(U4C-Y-Pad8)") (class "Default")
      (node (ref "U4") (pin "8") (pinfunction "Y_8") (pintype "bidirectional"))
    )
    (net (code "78") (name "unconnected-(U4D-A-Pad12)") (class "Default")
      (node (ref "U4") (pin "12") (pinfunction "A_12") (pintype "input"))
    )
    (net (code "79") (name "unconnected-(U4D-B-Pad13)") (class "Default")
      (node (ref "U4") (pin "13") (pinfunction "B_13") (pintype "input"))
    )
    (net (code "80") (name "unconnected-(U4D-Y-Pad11)") (class "Default")
      (node (ref "U4") (pin "11") (pinfunction "Y_11") (pintype "bidirectional"))
    )
  )
)
